# Shield_Schematic_v2.net
KiCad netlist of a schematic drawn in Altium Designer
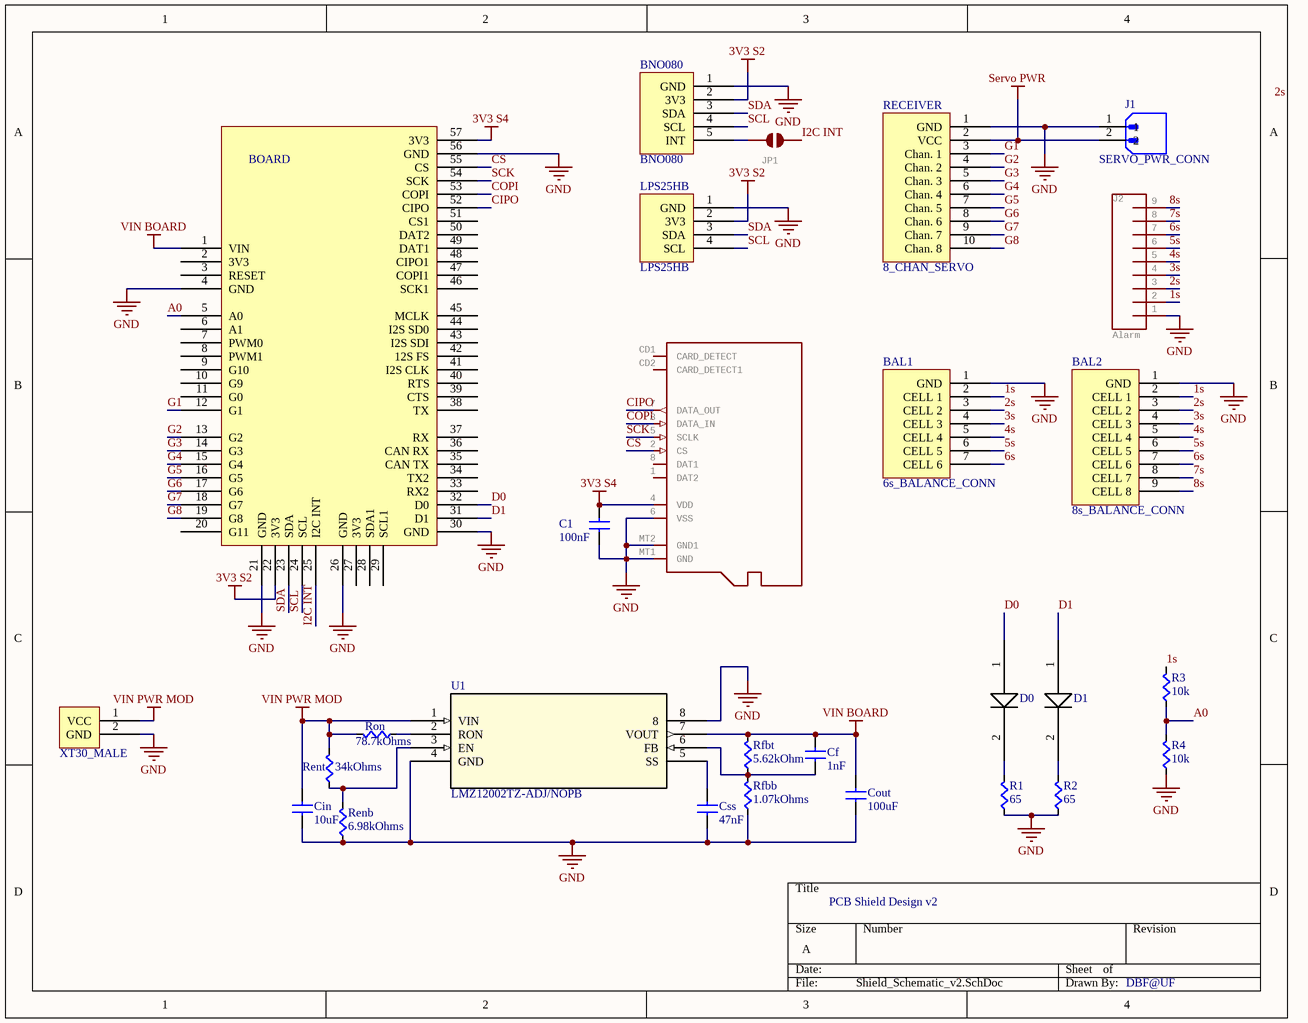
[diagram p0: Shield_Schematic_v2.SchDoc]

(export (version "E")
  (design (tool "Eeschema 10.0.6"))
  (components
    (comp (ref "BAL1")
      (value "6s_BALANCE_CONN")
      (footprint "B7B-XH-A")
      (libsource (lib "DBF") (part "6s_BALANCE_CONN"))
    )
    (comp (ref "BAL2")
      (value "8s_BALANCE_CONN")
      (footprint "B9B-XH-A")
      (libsource (lib "DBF") (part "8s_BALANCE_CONN"))
    )
    (comp (ref "BNO080")
      (value "BNO080")
      (footprint "BNO080")
      (description "BNO080 Breakout Board")
      (libsource (lib "DBF") (part "BNO080"))
    )
    (comp (ref "BOARD") (value "SHIELD") (footprint "Shield") (libsource (lib "DBF") (part "SHIELD")))
    (comp (ref "C1")
      (value "100nF")
      (footprint "CAPC 0603")
      (fields (field (name "Comment") "Cap (0603)"))
      (libsource (lib "DBF") (part "Cap (0603)"))
    )
    (comp (ref "Cf")
      (value "1nF")
      (footprint "CAPC 0402")
      (fields (field (name "Comment") "Cap (0402)"))
      (libsource (lib "DBF") (part "Cap (0402)"))
    )
    (comp (ref "Cin")
      (value "10uF")
      (footprint "CAPC 0805")
      (fields (field (name "Comment") "Cap (0805)"))
      (libsource (lib "DBF") (part "Cap (0805)"))
    )
    (comp (ref "Cout")
      (value "100uF")
      (footprint "CAPC 1206")
      (fields (field (name "Comment") "Cap (1206)"))
      (libsource (lib "DBF") (part "Cap (1206)"))
    )
    (comp (ref "Css")
      (value "47nF")
      (footprint "CAPC 0805")
      (fields (field (name "Comment") "Cap (0805)"))
      (libsource (lib "DBF") (part "Cap (0805)"))
    )
    (comp (ref "D0") (value "LED (0805)") (footprint "LED 0805") (libsource (lib "DBF") (part "LED (0805)")))
    (comp (ref "D1") (value "LED (0805)") (footprint "LED 0805") (libsource (lib "DBF") (part "LED (0805)")))
    (comp (ref "J1")
      (value "SERVO_PWR_CONN")
      (footprint "1053091102")
      (description "Connector Header Through Hole 2 position 0.098 (2.50mm)")
      (fields (field (name "MF") "Molex") (field (name "MP") "1053091102"))
      (libsource (lib "DBF") (part "SERVO_PWR_CONN"))
    )
    (comp (ref "J2")
      (value "Alarm")
      (footprint "1X09_NO_SILK")
      (libsource (lib "DBF") (part "CONN_09NO_SILK_FEMALE_PTH"))
    )
    (comp (ref "JP1")
      (value "Normally open jumper    This jumper has two pads in close proximity to each other. Apply solder to close the connection.   Round pads are easier to solder for beginners, but are a lot larger.   SparkFun Product that uses the round pads:  SparkFun EL Sequencer")
      (footprint "SMT-JUMPER_2_NO_SILK")
      (libsource (lib "DBF") (part "JUMPER-SMT_2_NO_SILK"))
    )
    (comp (ref "LPS25HB")
      (value "LPS25HB")
      (footprint "LPS25HB")
      (description "LPS25HB Breakout Board")
      (libsource (lib "DBF") (part "LPS25HB"))
    )
    (comp (ref "R1")
      (value "65")
      (footprint "RES 0603")
      (fields (field (name "Comment") "Res (0603)"))
      (libsource (lib "DBF") (part "Res (0603)"))
    )
    (comp (ref "R2")
      (value "65")
      (footprint "RES 0603")
      (fields (field (name "Comment") "Res (0603)"))
      (libsource (lib "DBF") (part "Res (0603)"))
    )
    (comp (ref "R3")
      (value "10k")
      (footprint "RES 0603")
      (fields (field (name "Comment") "Res (0603)"))
      (libsource (lib "DBF") (part "Res (0603)"))
    )
    (comp (ref "R4")
      (value "10k")
      (footprint "RES 0603")
      (fields (field (name "Comment") "Res (0603)"))
      (libsource (lib "DBF") (part "Res (0603)"))
    )
    (comp (ref "RECEIVER")
      (value "8_CHAN_SERVO")
      (footprint "8_CHAN_SERVO")
      (libsource (lib "DBF") (part "8_CHAN_SERVO"))
    )
    (comp (ref "Renb")
      (value "6.98kOhms")
      (footprint "RES 0805")
      (fields (field (name "Comment") "Res (0805)"))
      (libsource (lib "DBF") (part "Res (0805)"))
    )
    (comp (ref "Rent")
      (value "34kOhms")
      (footprint "RES 0805")
      (fields (field (name "Comment") "Res (0805)"))
      (libsource (lib "DBF") (part "Res (0805)"))
    )
    (comp (ref "Rfbb")
      (value "1.07kOhms")
      (footprint "RES 0805")
      (fields (field (name "Comment") "Res (0805)"))
      (libsource (lib "DBF") (part "Res (0805)"))
    )
    (comp (ref "Rfbt")
      (value "5.62kOhm")
      (footprint "RES 0805")
      (fields (field (name "Comment") "Res (0805)"))
      (libsource (lib "DBF") (part "Res (0805)"))
    )
    (comp (ref "Ron")
      (value "78.7kOhms")
      (footprint "RES 0805")
      (fields (field (name "Comment") "Res (0805)"))
      (libsource (lib "DBF") (part "Res (0805)"))
    )
    (comp (ref "U1")
      (value "LMZ12002TZ-ADJ/NOPB")
      (footprint "LMZ12002")
      (description "2A SIMPLE SWITCHER® Power Module with 20V Maximum Input Voltage")
      (fields
        (field (name "MANUFACTURER") "Texas Instruments")
        (field (name "COPYRIGHT") "Copyright (C) 2018 Accelerated Designs. All rights reserved")
      )
      (libsource (lib "DBF") (part "LMZ12002TZ-ADJ/NOPB"))
    )
    (comp (ref "uSD")
      (value "Micro-SD / Transflash card holder with SPI pinout   For the 3M # 2908-05WB-MG and/or 4UCON #19656 push-push type")
      (footprint "MICROSD")
      (libsource (lib "DBF") (part "MICROSD"))
    )
    (comp (ref "XT30") (value "XT30_MALE") (footprint "XT30_MALE") (libsource (lib "DBF") (part "XT30_MALE")))
  )
  (nets
    (net (code "1") (name "/1s") (class "Default")
      (node (ref "BAL1") (pin "2") (pinfunction "CELL_1_2") (pintype "passive"))
      (node (ref "BAL2") (pin "2") (pinfunction "CELL_1_2") (pintype "passive"))
      (node (ref "J2") (pin "2") (pinfunction "2_2") (pintype "passive"))
      (node (ref "R3") (pin "1") (pinfunction "A_1") (pintype "passive"))
    )
    (net (code "2") (name "/2s") (class "Default")
      (node (ref "BAL1") (pin "3") (pinfunction "CELL_2_3") (pintype "passive"))
      (node (ref "BAL2") (pin "3") (pinfunction "CELL_2_3") (pintype "passive"))
      (node (ref "J2") (pin "3") (pinfunction "3_3") (pintype "passive"))
    )
    (net (code "3") (name "/3s") (class "Default")
      (node (ref "BAL1") (pin "4") (pinfunction "CELL_3_4") (pintype "passive"))
      (node (ref "BAL2") (pin "4") (pinfunction "CELL_3_4") (pintype "passive"))
      (node (ref "J2") (pin "4") (pinfunction "4_4") (pintype "passive"))
    )
    (net (code "4") (name "/4s") (class "Default")
      (node (ref "BAL1") (pin "5") (pinfunction "CELL_4_5") (pintype "passive"))
      (node (ref "BAL2") (pin "5") (pinfunction "CELL_4_5") (pintype "passive"))
      (node (ref "J2") (pin "5") (pinfunction "5_5") (pintype "passive"))
    )
    (net (code "5") (name "/5s") (class "Default")
      (node (ref "BAL1") (pin "6") (pinfunction "CELL_5_6") (pintype "passive"))
      (node (ref "BAL2") (pin "6") (pinfunction "CELL_5_6") (pintype "passive"))
      (node (ref "J2") (pin "6") (pinfunction "6_6") (pintype "passive"))
    )
    (net (code "6") (name "/6s") (class "Default")
      (node (ref "BAL1") (pin "7") (pinfunction "CELL_6_7") (pintype "passive"))
      (node (ref "BAL2") (pin "7") (pinfunction "CELL_6_7") (pintype "passive"))
      (node (ref "J2") (pin "7") (pinfunction "7_7") (pintype "passive"))
    )
    (net (code "7") (name "/7s") (class "Default")
      (node (ref "BAL2") (pin "8") (pinfunction "CELL_7_8") (pintype "passive"))
      (node (ref "J2") (pin "8") (pinfunction "8_8") (pintype "passive"))
    )
    (net (code "8") (name "/8s") (class "Default")
      (node (ref "BAL2") (pin "9") (pinfunction "CELL_8_9") (pintype "passive"))
      (node (ref "J2") (pin "9") (pinfunction "9_9") (pintype "passive"))
    )
    (net (code "9") (name "/A0") (class "Default")
      (node (ref "BOARD") (pin "5") (pinfunction "A0_5") (pintype "passive"))
      (node (ref "R3") (pin "2") (pinfunction "B_2") (pintype "passive"))
      (node (ref "R4") (pin "1") (pinfunction "A_1") (pintype "passive"))
    )
    (net (code "10") (name "/CIPO") (class "Default")
      (node (ref "BOARD") (pin "52") (pinfunction "CIPO_52") (pintype "passive"))
      (node (ref "uSD") (pin "7") (pinfunction "DATA_OUT_7") (pintype "output"))
    )
    (net (code "11") (name "/COPI") (class "Default")
      (node (ref "BOARD") (pin "53") (pinfunction "COPI_53") (pintype "passive"))
      (node (ref "uSD") (pin "3") (pinfunction "DATA_IN_3") (pintype "input"))
    )
    (net (code "12") (name "/CS") (class "Default")
      (node (ref "BOARD") (pin "55") (pinfunction "CS_55") (pintype "passive"))
      (node (ref "uSD") (pin "2") (pinfunction "CS_2") (pintype "input"))
    )
    (net (code "13") (name "/D0") (class "Default")
      (node (ref "BOARD") (pin "32") (pinfunction "D0_32") (pintype "passive"))
      (node (ref "D0") (pin "1") (pinfunction "+_1") (pintype "passive"))
    )
    (net (code "14") (name "/D1") (class "Default")
      (node (ref "BOARD") (pin "31") (pinfunction "D1_31") (pintype "passive"))
      (node (ref "D1") (pin "1") (pinfunction "+_1") (pintype "passive"))
    )
    (net (code "15") (name "/G1") (class "Default")
      (node (ref "BOARD") (pin "12") (pinfunction "G1_12") (pintype "passive"))
      (node (ref "RECEIVER") (pin "3") (pinfunction "Chan._1_3") (pintype "passive"))
    )
    (net (code "16") (name "/G2") (class "Default")
      (node (ref "BOARD") (pin "13") (pinfunction "G2_13") (pintype "passive"))
      (node (ref "RECEIVER") (pin "4") (pinfunction "Chan._2_4") (pintype "passive"))
    )
    (net (code "17") (name "/G3") (class "Default")
      (node (ref "BOARD") (pin "14") (pinfunction "G3_14") (pintype "passive"))
      (node (ref "RECEIVER") (pin "5") (pinfunction "Chan._3_5") (pintype "passive"))
    )
    (net (code "18") (name "/G4") (class "Default")
      (node (ref "BOARD") (pin "15") (pinfunction "G4_15") (pintype "passive"))
      (node (ref "RECEIVER") (pin "6") (pinfunction "Chan._4_6") (pintype "passive"))
    )
    (net (code "19") (name "/G5") (class "Default")
      (node (ref "BOARD") (pin "16") (pinfunction "G5_16") (pintype "passive"))
      (node (ref "RECEIVER") (pin "7") (pinfunction "Chan._5_7") (pintype "passive"))
    )
    (net (code "20") (name "/G6") (class "Default")
      (node (ref "BOARD") (pin "17") (pinfunction "G6_17") (pintype "passive"))
      (node (ref "RECEIVER") (pin "8") (pinfunction "Chan._6_8") (pintype "passive"))
    )
    (net (code "21") (name "/G7") (class "Default")
      (node (ref "BOARD") (pin "18") (pinfunction "G7_18") (pintype "passive"))
      (node (ref "RECEIVER") (pin "9") (pinfunction "Chan._7_9") (pintype "passive"))
    )
    (net (code "22") (name "/G8") (class "Default")
      (node (ref "BOARD") (pin "19") (pinfunction "G8_19") (pintype "passive"))
      (node (ref "RECEIVER") (pin "10") (pinfunction "Chan._8_10") (pintype "passive"))
    )
    (net (code "23") (name "/I2C INT") (class "Default")
      (node (ref "BOARD") (pin "25") (pinfunction "I2C_INT_25") (pintype "passive"))
      (node (ref "JP1") (pin "2") (pinfunction "2_2") (pintype "passive"))
    )
    (net (code "24") (name "/SCK") (class "Default")
      (node (ref "BOARD") (pin "54") (pinfunction "SCK_54") (pintype "passive"))
      (node (ref "uSD") (pin "5") (pinfunction "SCLK_5") (pintype "input"))
    )
    (net (code "25") (name "/SCL") (class "Default")
      (node (ref "BNO080") (pin "4") (pinfunction "SCL_4") (pintype "passive"))
      (node (ref "BOARD") (pin "24") (pinfunction "SCL_24") (pintype "passive"))
      (node (ref "LPS25HB") (pin "4") (pinfunction "SCL_4") (pintype "passive"))
    )
    (net (code "26") (name "/SDA") (class "Default")
      (node (ref "BNO080") (pin "3") (pinfunction "SDA_3") (pintype "passive"))
      (node (ref "BOARD") (pin "23") (pinfunction "SDA_23") (pintype "passive"))
      (node (ref "LPS25HB") (pin "3") (pinfunction "SDA_3") (pintype "passive"))
    )
    (net (code "27") (name "3V3 S2") (class "Default")
      (node (ref "BNO080") (pin "2") (pinfunction "3V3_2") (pintype "passive"))
      (node (ref "BOARD") (pin "22") (pinfunction "3V3_22") (pintype "passive"))
      (node (ref "LPS25HB") (pin "2") (pinfunction "3V3_2") (pintype "passive"))
    )
    (net (code "28") (name "3V3 S4") (class "Default")
      (node (ref "BOARD") (pin "57") (pinfunction "3V3_57") (pintype "passive"))
      (node (ref "C1") (pin "1") (pinfunction "A_1") (pintype "passive"))
      (node (ref "uSD") (pin "4") (pinfunction "VDD_4") (pintype "power_in"))
    )
    (net (code "29") (name "GND") (class "Default")
      (node (ref "BAL1") (pin "1") (pinfunction "GND_1") (pintype "passive"))
      (node (ref "BAL2") (pin "1") (pinfunction "GND_1") (pintype "passive"))
      (node (ref "BNO080") (pin "1") (pinfunction "GND_1") (pintype "passive"))
      (node (ref "BOARD") (pin "21") (pinfunction "GND_21") (pintype "passive"))
      (node (ref "BOARD") (pin "26") (pinfunction "GND_26") (pintype "passive"))
      (node (ref "BOARD") (pin "30") (pinfunction "GND_30") (pintype "passive"))
      (node (ref "BOARD") (pin "4") (pinfunction "GND_4") (pintype "passive"))
      (node (ref "BOARD") (pin "56") (pinfunction "GND_56") (pintype "passive"))
      (node (ref "C1") (pin "2") (pinfunction "B_2") (pintype "passive"))
      (node (ref "Cin") (pin "2") (pinfunction "B_2") (pintype "passive"))
      (node (ref "Cout") (pin "2") (pinfunction "B_2") (pintype "passive"))
      (node (ref "Css") (pin "2") (pinfunction "B_2") (pintype "passive"))
      (node (ref "J1") (pin "1") (pinfunction "1_1") (pintype "passive"))
      (node (ref "J2") (pin "1") (pinfunction "1_1") (pintype "passive"))
      (node (ref "LPS25HB") (pin "1") (pinfunction "GND_1") (pintype "passive"))
      (node (ref "R1") (pin "2") (pinfunction "B_2") (pintype "passive"))
      (node (ref "R2") (pin "2") (pinfunction "B_2") (pintype "passive"))
      (node (ref "R4") (pin "2") (pinfunction "B_2") (pintype "passive"))
      (node (ref "RECEIVER") (pin "1") (pinfunction "GND_1") (pintype "passive"))
      (node (ref "Renb") (pin "2") (pinfunction "B_2") (pintype "passive"))
      (node (ref "Rfbb") (pin "2") (pinfunction "B_2") (pintype "passive"))
      (node (ref "U1") (pin "4") (pinfunction "GND_4") (pintype "power_in"))
      (node (ref "U1") (pin "8") (pinfunction "8_8") (pintype "passive"))
      (node (ref "XT30") (pin "2") (pinfunction "GND_2") (pintype "passive"))
      (node (ref "uSD") (pin "6") (pinfunction "VSS_6") (pintype "power_in"))
      (node (ref "uSD") (pin "MT1") (pinfunction "GND_MT1") (pintype "power_in"))
      (node (ref "uSD") (pin "MT2") (pinfunction "GND1_MT2") (pintype "power_in"))
    )
    (net (code "30") (name "Net-(BNO080-INT)") (class "Default")
      (node (ref "BNO080") (pin "5") (pinfunction "INT_5") (pintype "passive"))
      (node (ref "JP1") (pin "1") (pinfunction "1_1") (pintype "passive"))
    )
    (net (code "31") (name "Net-(Cf-B)") (class "Default")
      (node (ref "Cf") (pin "2") (pinfunction "B_2") (pintype "passive"))
      (node (ref "Rfbb") (pin "1") (pinfunction "A_1") (pintype "passive"))
      (node (ref "Rfbt") (pin "2") (pinfunction "B_2") (pintype "passive"))
      (node (ref "U1") (pin "6") (pinfunction "FB_6") (pintype "input"))
    )
    (net (code "32") (name "Net-(Css-A)") (class "Default")
      (node (ref "Css") (pin "1") (pinfunction "A_1") (pintype "passive"))
      (node (ref "U1") (pin "5") (pinfunction "SS_5") (pintype "passive"))
    )
    (net (code "33") (name "Net-(D0--)") (class "Default")
      (node (ref "D0") (pin "2") (pinfunction "-_2") (pintype "passive"))
      (node (ref "R1") (pin "1") (pinfunction "A_1") (pintype "passive"))
    )
    (net (code "34") (name "Net-(D1--)") (class "Default")
      (node (ref "D1") (pin "2") (pinfunction "-_2") (pintype "passive"))
      (node (ref "R2") (pin "1") (pinfunction "A_1") (pintype "passive"))
    )
    (net (code "35") (name "Net-(Renb-A)") (class "Default")
      (node (ref "Renb") (pin "1") (pinfunction "A_1") (pintype "passive"))
      (node (ref "Rent") (pin "2") (pinfunction "B_2") (pintype "passive"))
      (node (ref "U1") (pin "3") (pinfunction "EN_3") (pintype "input"))
    )
    (net (code "36") (name "Net-(Ron-B)") (class "Default")
      (node (ref "Ron") (pin "2") (pinfunction "B_2") (pintype "passive"))
      (node (ref "U1") (pin "2") (pinfunction "RON_2") (pintype "passive"))
    )
    (net (code "37") (name "Servo PWR") (class "Default")
      (node (ref "J1") (pin "2") (pinfunction "2_2") (pintype "passive"))
      (node (ref "RECEIVER") (pin "2") (pinfunction "VCC_2") (pintype "passive"))
    )
    (net (code "38") (name "VIN BOARD") (class "Default")
      (node (ref "BOARD") (pin "1") (pinfunction "VIN_1") (pintype "passive"))
      (node (ref "Cf") (pin "1") (pinfunction "A_1") (pintype "passive"))
      (node (ref "Cout") (pin "1") (pinfunction "A_1") (pintype "passive"))
      (node (ref "Rfbt") (pin "1") (pinfunction "A_1") (pintype "passive"))
      (node (ref "U1") (pin "7") (pinfunction "VOUT_7") (pintype "output"))
    )
    (net (code "39") (name "VIN PWR MOD") (class "Default")
      (node (ref "Cin") (pin "1") (pinfunction "A_1") (pintype "passive"))
      (node (ref "Rent") (pin "1") (pinfunction "A_1") (pintype "passive"))
      (node (ref "Ron") (pin "1") (pinfunction "A_1") (pintype "passive"))
      (node (ref "U1") (pin "1") (pinfunction "VIN_1") (pintype "input"))
      (node (ref "XT30") (pin "1") (pinfunction "VCC_1") (pintype "passive"))
    )
    (net (code "40") (name "unconnected-(BOARD-3V3-Pad2)") (class "Default")
      (node (ref "BOARD") (pin "2") (pinfunction "3V3_2") (pintype "passive"))
    )
    (net (code "41") (name "unconnected-(BOARD-3V3-Pad27)") (class "Default")
      (node (ref "BOARD") (pin "27") (pinfunction "3V3_27") (pintype "passive"))
    )
    (net (code "42") (name "unconnected-(BOARD-12S_FS-Pad42)") (class "Default")
      (node (ref "BOARD") (pin "42") (pinfunction "12S_FS_42") (pintype "passive"))
    )
    (net (code "43") (name "unconnected-(BOARD-A1-Pad6)") (class "Default")
      (node (ref "BOARD") (pin "6") (pinfunction "A1_6") (pintype "passive"))
    )
    (net (code "44") (name "unconnected-(BOARD-CAN_RX-Pad36)") (class "Default")
      (node (ref "BOARD") (pin "36") (pinfunction "CAN_RX_36") (pintype "passive"))
    )
    (net (code "45") (name "unconnected-(BOARD-CAN_TX-Pad35)") (class "Default")
      (node (ref "BOARD") (pin "35") (pinfunction "CAN_TX_35") (pintype "passive"))
    )
    (net (code "46") (name "unconnected-(BOARD-CIPO1-Pad48)") (class "Default")
      (node (ref "BOARD") (pin "48") (pinfunction "CIPO1_48") (pintype "passive"))
    )
    (net (code "47") (name "unconnected-(BOARD-COPI1-Pad47)") (class "Default")
      (node (ref "BOARD") (pin "47") (pinfunction "COPI1_47") (pintype "passive"))
    )
    (net (code "48") (name "unconnected-(BOARD-CS1-Pad51)") (class "Default")
      (node (ref "BOARD") (pin "51") (pinfunction "CS1_51") (pintype "passive"))
    )
    (net (code "49") (name "unconnected-(BOARD-CTS-Pad39)") (class "Default")
      (node (ref "BOARD") (pin "39") (pinfunction "CTS_39") (pintype "passive"))
    )
    (net (code "50") (name "unconnected-(BOARD-DAT1-Pad49)") (class "Default")
      (node (ref "BOARD") (pin "49") (pinfunction "DAT1_49") (pintype "passive"))
    )
    (net (code "51") (name "unconnected-(BOARD-DAT2-Pad50)") (class "Default")
      (node (ref "BOARD") (pin "50") (pinfunction "DAT2_50") (pintype "passive"))
    )
    (net (code "52") (name "unconnected-(BOARD-G0-Pad11)") (class "Default")
      (node (ref "BOARD") (pin "11") (pinfunction "G0_11") (pintype "passive"))
    )
    (net (code "53") (name "unconnected-(BOARD-G9-Pad10)") (class "Default")
      (node (ref "BOARD") (pin "10") (pinfunction "G9_10") (pintype "passive"))
    )
    (net (code "54") (name "unconnected-(BOARD-G10-Pad9)") (class "Default")
      (node (ref "BOARD") (pin "9") (pinfunction "G10_9") (pintype "passive"))
    )
    (net (code "55") (name "unconnected-(BOARD-G11-Pad20)") (class "Default")
      (node (ref "BOARD") (pin "20") (pinfunction "G11_20") (pintype "passive"))
    )
    (net (code "56") (name "unconnected-(BOARD-I2S_CLK-Pad41)") (class "Default")
      (node (ref "BOARD") (pin "41") (pinfunction "I2S_CLK_41") (pintype "passive"))
    )
    (net (code "57") (name "unconnected-(BOARD-I2S_SD0-Pad44)") (class "Default")
      (node (ref "BOARD") (pin "44") (pinfunction "I2S_SD0_44") (pintype "passive"))
    )
    (net (code "58") (name "unconnected-(BOARD-I2S_SDI-Pad43)") (class "Default")
      (node (ref "BOARD") (pin "43") (pinfunction "I2S_SDI_43") (pintype "passive"))
    )
    (net (code "59") (name "unconnected-(BOARD-MCLK-Pad45)") (class "Default")
      (node (ref "BOARD") (pin "45") (pinfunction "MCLK_45") (pintype "passive"))
    )
    (net (code "60") (name "unconnected-(BOARD-PWM0-Pad7)") (class "Default")
      (node (ref "BOARD") (pin "7") (pinfunction "PWM0_7") (pintype "passive"))
    )
    (net (code "61") (name "unconnected-(BOARD-PWM1-Pad8)") (class "Default")
      (node (ref "BOARD") (pin "8") (pinfunction "PWM1_8") (pintype "passive"))
    )
    (net (code "62") (name "unconnected-(BOARD-RESET-Pad3)") (class "Default")
      (node (ref "BOARD") (pin "3") (pinfunction "RESET_3") (pintype "passive"))
    )
    (net (code "63") (name "unconnected-(BOARD-RTS-Pad40)") (class "Default")
      (node (ref "BOARD") (pin "40") (pinfunction "RTS_40") (pintype "passive"))
    )
    (net (code "64") (name "unconnected-(BOARD-RX-Pad37)") (class "Default")
      (node (ref "BOARD") (pin "37") (pinfunction "RX_37") (pintype "passive"))
    )
    (net (code "65") (name "unconnected-(BOARD-RX2-Pad33)") (class "Default")
      (node (ref "BOARD") (pin "33") (pinfunction "RX2_33") (pintype "passive"))
    )
    (net (code "66") (name "unconnected-(BOARD-SCK1-Pad46)") (class "Default")
      (node (ref "BOARD") (pin "46") (pinfunction "SCK1_46") (pintype "passive"))
    )
    (net (code "67") (name "unconnected-(BOARD-SCL1-Pad29)") (class "Default")
      (node (ref "BOARD") (pin "29") (pinfunction "SCL1_29") (pintype "passive"))
    )
    (net (code "68") (name "unconnected-(BOARD-SDA1-Pad28)") (class "Default")
      (node (ref "BOARD") (pin "28") (pinfunction "SDA1_28") (pintype "passive"))
    )
    (net (code "69") (name "unconnected-(BOARD-TX-Pad38)") (class "Default")
      (node (ref "BOARD") (pin "38") (pinfunction "TX_38") (pintype "passive"))
    )
    (net (code "70") (name "unconnected-(BOARD-TX2-Pad34)") (class "Default")
      (node (ref "BOARD") (pin "34") (pinfunction "TX2_34") (pintype "passive"))
    )
    (net (code "71") (name "unconnected-(uSD-CARD_DETECT-PadCD1)") (class "Default")
      (node (ref "uSD") (pin "CD1") (pinfunction "CARD_DETECT_CD1") (pintype "passive"))
    )
    (net (code "72") (name "unconnected-(uSD-CARD_DETECT1-PadCD2)") (class "Default")
      (node (ref "uSD") (pin "CD2") (pinfunction "CARD_DETECT1_CD2") (pintype "passive"))
    )
    (net (code "73") (name "unconnected-(uSD-DAT1-Pad8)") (class "Default")
      (node (ref "uSD") (pin "8") (pinfunction "DAT1_8") (pintype "bidirectional"))
    )
    (net (code "74") (name "unconnected-(uSD-DAT2-Pad1)") (class "Default")
      (node (ref "uSD") (pin "1") (pinfunction "DAT2_1") (pintype "bidirectional"))
    )
  )
)
